# m1284prog.net
KiCad netlist of a schematic drawn in EAGLE
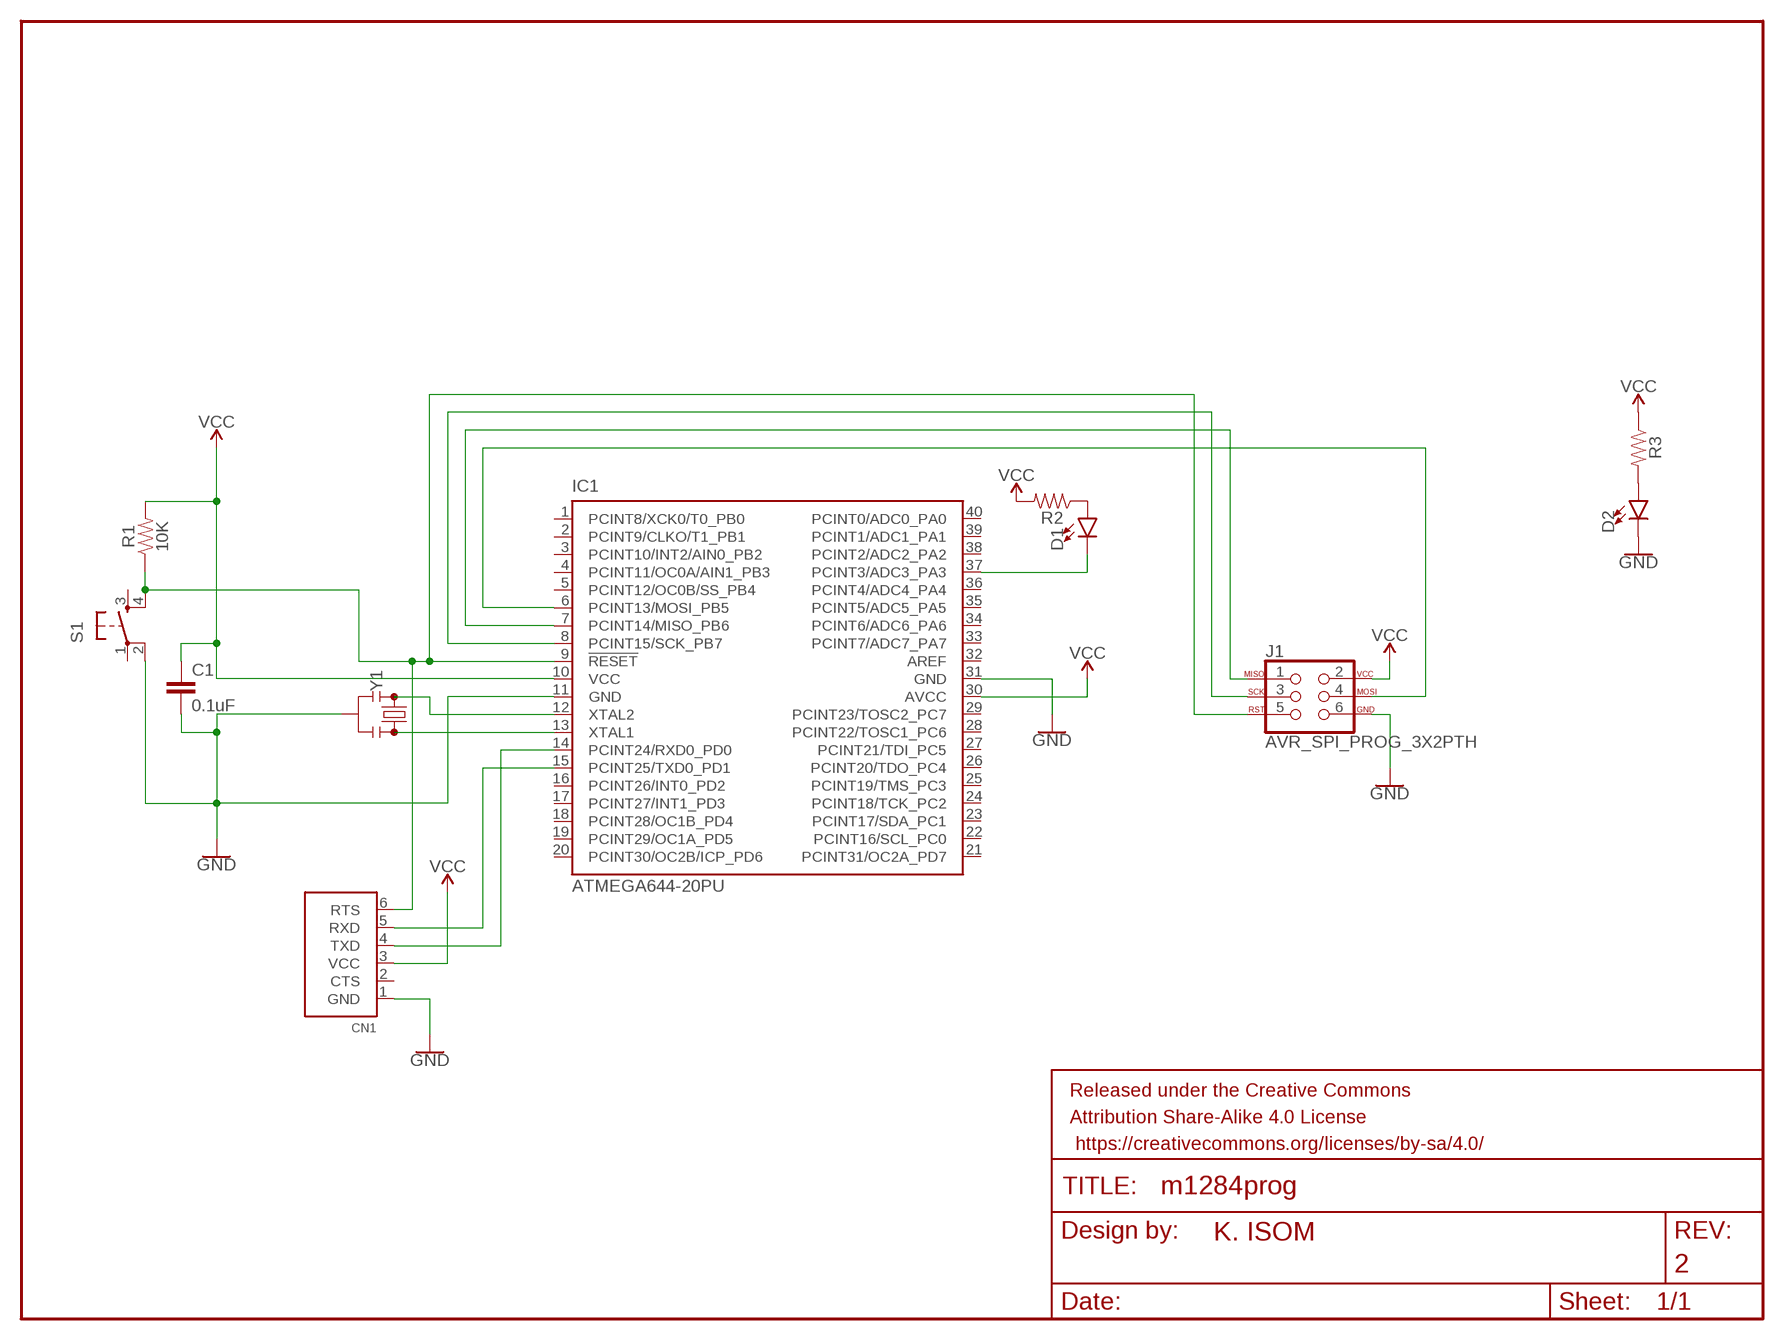
[diagram p0: schematic, sheet 1]

(export (version "E")
  (design (tool "Eeschema 10.0.6"))
  (components
    (comp (ref "C1")
      (value "0.1uF")
      (footprint "eagle-import:C2.5-3")
      (libsource (lib "eagle-import") (part "C2,5-3"))
    )
    (comp (ref "CN1")
      (value "FTDIUSBCABLE")
      (footprint "eagle-import:1X06_ROUND")
      (libsource (lib "eagle-import") (part "FTDIUSBCABLE"))
    )
    (comp (ref "D1")
      (value "LED3MM")
      (footprint "eagle-import:LED_3MM")
      (libsource (lib "eagle-import") (part "LED3MM"))
    )
    (comp (ref "D2")
      (value "LED3MM")
      (footprint "eagle-import:LED_3MM")
      (libsource (lib "eagle-import") (part "LED3MM"))
    )
    (comp (ref "FRAME1")
      (value "FRAME-LETTER")
      (footprint "eagle-import:CREATIVE_COMMONS")
      (fields (field (name "DESIGNER") "K. ISOM") (field (name "REV") "2"))
      (libsource (lib "eagle-import") (part "FRAME-LETTER"))
    )
    (comp (ref "IC1")
      (value "ATMEGA644-20PU")
      (footprint "eagle-import:DIL40")
      (libsource (lib "eagle-import") (part "ATMEGA644-PU20"))
    )
    (comp (ref "J1")
      (value "AVR_SPI_PROG_3X2PTH")
      (footprint "eagle-import:2X3")
      (libsource (lib "eagle-import") (part "AVR_SPI_PROG_3X2PTH"))
    )
    (comp (ref "R1")
      (value "10K")
      (footprint "eagle-import:AXIAL-0.3")
      (libsource (lib "eagle-import") (part "RESISTORAXIAL-0.3"))
    )
    (comp (ref "R2")
      (value "RESISTORAXIAL-0.3")
      (footprint "eagle-import:AXIAL-0.3")
      (libsource (lib "eagle-import") (part "RESISTORAXIAL-0.3"))
    )
    (comp (ref "R3")
      (value "RESISTORAXIAL-0.3")
      (footprint "eagle-import:AXIAL-0.3")
      (libsource (lib "eagle-import") (part "RESISTORAXIAL-0.3"))
    )
    (comp (ref "S1")
      (value "TAC_SWITCHPTH")
      (footprint "eagle-import:TACTILE-PTH")
      (libsource (lib "eagle-import") (part "TAC_SWITCHPTH"))
    )
    (comp (ref "Y1")
      (value "RESONATORPTH-7.6X3.8")
      (footprint "eagle-import:RESONATOR-PTH-7.6X3.8")
      (libsource (lib "eagle-import") (part "RESONATORPTH-7.6X3.8"))
    )
  )
  (nets
    (net (code "1") (name "GND") (class "Default")
      (node (ref "C1") (pin "2") (pinfunction "2_2") (pintype "passive"))
      (node (ref "CN1") (pin "1") (pinfunction "GND_1") (pintype "bidirectional"))
      (node (ref "D2") (pin "K") (pinfunction "C_K") (pintype "passive"))
      (node (ref "IC1") (pin "11") (pinfunction "GND_11") (pintype "power_in"))
      (node (ref "IC1") (pin "31") (pinfunction "GND_31") (pintype "power_in"))
      (node (ref "J1") (pin "6") (pinfunction "6_6") (pintype "passive"))
      (node (ref "S1") (pin "2") (pinfunction "2_2") (pintype "passive"))
      (node (ref "Y1") (pin "2") (pinfunction "2_2") (pintype "passive"))
    )
    (net (code "2") (name "Net-(CN1-RTS)") (class "Default")
      (node (ref "CN1") (pin "6") (pinfunction "RTS_6") (pintype "bidirectional"))
      (node (ref "IC1") (pin "9") (pinfunction "~{RESET}_9") (pintype "input"))
      (node (ref "J1") (pin "5") (pinfunction "5_5") (pintype "passive"))
      (node (ref "R1") (pin "P$1") (pinfunction "1_P$1") (pintype "passive"))
      (node (ref "S1") (pin "4") (pinfunction "4_4") (pintype "passive"))
    )
    (net (code "3") (name "Net-(CN1-RXD)") (class "Default")
      (node (ref "CN1") (pin "5") (pinfunction "RXD_5") (pintype "bidirectional"))
      (node (ref "IC1") (pin "15") (pinfunction "PCINT25/TXD0_PD1_15") (pintype "bidirectional"))
    )
    (net (code "4") (name "Net-(CN1-TXD)") (class "Default")
      (node (ref "CN1") (pin "4") (pinfunction "TXD_4") (pintype "bidirectional"))
      (node (ref "IC1") (pin "14") (pinfunction "PCINT24/RXD0_PD0_14") (pintype "bidirectional"))
    )
    (net (code "5") (name "Net-(D1-C)") (class "Default")
      (node (ref "D1") (pin "K") (pinfunction "C_K") (pintype "passive"))
      (node (ref "IC1") (pin "37") (pinfunction "PCINT3/ADC3_PA3_37") (pintype "bidirectional"))
    )
    (net (code "6") (name "Net-(IC1-PCINT13{slash}MOSI_PB5)") (class "Default")
      (node (ref "IC1") (pin "6") (pinfunction "PCINT13/MOSI_PB5_6") (pintype "bidirectional"))
      (node (ref "J1") (pin "4") (pinfunction "4_4") (pintype "passive"))
    )
    (net (code "7") (name "Net-(IC1-PCINT14{slash}MISO_PB6)") (class "Default")
      (node (ref "IC1") (pin "7") (pinfunction "PCINT14/MISO_PB6_7") (pintype "bidirectional"))
      (node (ref "J1") (pin "1") (pinfunction "1_1") (pintype "passive"))
    )
    (net (code "8") (name "Net-(IC1-PCINT15{slash}SCK_PB7)") (class "Default")
      (node (ref "IC1") (pin "8") (pinfunction "PCINT15/SCK_PB7_8") (pintype "bidirectional"))
      (node (ref "J1") (pin "3") (pinfunction "3_3") (pintype "passive"))
    )
    (net (code "9") (name "Net-(IC1-XTAL1)") (class "Default")
      (node (ref "IC1") (pin "13") (pinfunction "XTAL1_13") (pintype "input"))
      (node (ref "Y1") (pin "3") (pinfunction "3_3") (pintype "passive"))
    )
    (net (code "10") (name "Net-(IC1-XTAL2)") (class "Default")
      (node (ref "IC1") (pin "12") (pinfunction "XTAL2_12") (pintype "output"))
      (node (ref "Y1") (pin "1") (pinfunction "1_1") (pintype "passive"))
    )
    (net (code "11") (name "Net-(R2-1)") (class "Default")
      (node (ref "D1") (pin "A") (pinfunction "A_A") (pintype "passive"))
      (node (ref "R2") (pin "P$1") (pinfunction "1_P$1") (pintype "passive"))
    )
    (net (code "12") (name "Net-(R3-2)") (class "Default")
      (node (ref "D2") (pin "A") (pinfunction "A_A") (pintype "passive"))
      (node (ref "R3") (pin "P$2") (pinfunction "2_P$2") (pintype "passive"))
    )
    (net (code "13") (name "VCC") (class "Default")
      (node (ref "C1") (pin "1") (pinfunction "1_1") (pintype "passive"))
      (node (ref "CN1") (pin "3") (pinfunction "VCC_3") (pintype "bidirectional"))
      (node (ref "IC1") (pin "10") (pinfunction "VCC_10") (pintype "power_in"))
      (node (ref "IC1") (pin "30") (pinfunction "AVCC_30") (pintype "power_in"))
      (node (ref "J1") (pin "2") (pinfunction "2_2") (pintype "passive"))
      (node (ref "R1") (pin "P$2") (pinfunction "2_P$2") (pintype "passive"))
      (node (ref "R2") (pin "P$2") (pinfunction "2_P$2") (pintype "passive"))
      (node (ref "R3") (pin "P$1") (pinfunction "1_P$1") (pintype "passive"))
    )
    (net (code "14") (name "unconnected-(CN1-CTS-Pad2)") (class "Default")
      (node (ref "CN1") (pin "2") (pinfunction "CTS_2") (pintype "bidirectional"))
    )
    (net (code "15") (name "unconnected-(IC1-AREF-Pad32)") (class "Default")
      (node (ref "IC1") (pin "32") (pinfunction "AREF_32") (pintype "passive"))
    )
    (net (code "16") (name "unconnected-(IC1-PCINT0{slash}ADC0_PA0-Pad40)") (class "Default")
      (node (ref "IC1") (pin "40") (pinfunction "PCINT0/ADC0_PA0_40") (pintype "bidirectional"))
    )
    (net (code "17") (name "unconnected-(IC1-PCINT1{slash}ADC1_PA1-Pad39)") (class "Default")
      (node (ref "IC1") (pin "39") (pinfunction "PCINT1/ADC1_PA1_39") (pintype "bidirectional"))
    )
    (net (code "18") (name "unconnected-(IC1-PCINT2{slash}ADC2_PA2-Pad38)") (class "Default")
      (node (ref "IC1") (pin "38") (pinfunction "PCINT2/ADC2_PA2_38") (pintype "bidirectional"))
    )
    (net (code "19") (name "unconnected-(IC1-PCINT4{slash}ADC4_PA4-Pad36)") (class "Default")
      (node (ref "IC1") (pin "36") (pinfunction "PCINT4/ADC4_PA4_36") (pintype "bidirectional"))
    )
    (net (code "20") (name "unconnected-(IC1-PCINT5{slash}ADC5_PA5-Pad35)") (class "Default")
      (node (ref "IC1") (pin "35") (pinfunction "PCINT5/ADC5_PA5_35") (pintype "bidirectional"))
    )
    (net (code "21") (name "unconnected-(IC1-PCINT6{slash}ADC6_PA6-Pad34)") (class "Default")
      (node (ref "IC1") (pin "34") (pinfunction "PCINT6/ADC6_PA6_34") (pintype "bidirectional"))
    )
    (net (code "22") (name "unconnected-(IC1-PCINT7{slash}ADC7_PA7-Pad33)") (class "Default")
      (node (ref "IC1") (pin "33") (pinfunction "PCINT7/ADC7_PA7_33") (pintype "bidirectional"))
    )
    (net (code "23") (name "unconnected-(IC1-PCINT8{slash}XCK0{slash}T0_PB0-Pad1)") (class "Default")
      (node (ref "IC1") (pin "1") (pinfunction "PCINT8/XCK0/T0_PB0_1") (pintype "bidirectional"))
    )
    (net (code "24") (name "unconnected-(IC1-PCINT9{slash}CLKO{slash}T1_PB1-Pad2)") (class "Default")
      (node (ref "IC1") (pin "2") (pinfunction "PCINT9/CLKO/T1_PB1_2") (pintype "bidirectional"))
    )
    (net (code "25") (name "unconnected-(IC1-PCINT10{slash}INT2{slash}AIN0_PB2-Pad3)") (class "Default")
      (node (ref "IC1") (pin "3") (pinfunction "PCINT10/INT2/AIN0_PB2_3") (pintype "bidirectional"))
    )
    (net (code "26") (name "unconnected-(IC1-PCINT11{slash}OC0A{slash}AIN1_PB3-Pad4)") (class "Default")
      (node (ref "IC1") (pin "4") (pinfunction "PCINT11/OC0A/AIN1_PB3_4") (pintype "bidirectional"))
    )
    (net (code "27") (name "unconnected-(IC1-PCINT12{slash}OC0B{slash}SS_PB4-Pad5)") (class "Default")
      (node (ref "IC1") (pin "5") (pinfunction "PCINT12/OC0B/SS_PB4_5") (pintype "bidirectional"))
    )
    (net (code "28") (name "unconnected-(IC1-PCINT16{slash}SCL_PC0-Pad22)") (class "Default")
      (node (ref "IC1") (pin "22") (pinfunction "PCINT16/SCL_PC0_22") (pintype "bidirectional"))
    )
    (net (code "29") (name "unconnected-(IC1-PCINT17{slash}SDA_PC1-Pad23)") (class "Default")
      (node (ref "IC1") (pin "23") (pinfunction "PCINT17/SDA_PC1_23") (pintype "bidirectional"))
    )
    (net (code "30") (name "unconnected-(IC1-PCINT18{slash}TCK_PC2-Pad24)") (class "Default")
      (node (ref "IC1") (pin "24") (pinfunction "PCINT18/TCK_PC2_24") (pintype "bidirectional"))
    )
    (net (code "31") (name "unconnected-(IC1-PCINT19{slash}TMS_PC3-Pad25)") (class "Default")
      (node (ref "IC1") (pin "25") (pinfunction "PCINT19/TMS_PC3_25") (pintype "bidirectional"))
    )
    (net (code "32") (name "unconnected-(IC1-PCINT20{slash}TDO_PC4-Pad26)") (class "Default")
      (node (ref "IC1") (pin "26") (pinfunction "PCINT20/TDO_PC4_26") (pintype "bidirectional"))
    )
    (net (code "33") (name "unconnected-(IC1-PCINT21{slash}TDI_PC5-Pad27)") (class "Default")
      (node (ref "IC1") (pin "27") (pinfunction "PCINT21/TDI_PC5_27") (pintype "bidirectional"))
    )
    (net (code "34") (name "unconnected-(IC1-PCINT22{slash}TOSC1_PC6-Pad28)") (class "Default")
      (node (ref "IC1") (pin "28") (pinfunction "PCINT22/TOSC1_PC6_28") (pintype "bidirectional"))
    )
    (net (code "35") (name "unconnected-(IC1-PCINT23{slash}TOSC2_PC7-Pad29)") (class "Default")
      (node (ref "IC1") (pin "29") (pinfunction "PCINT23/TOSC2_PC7_29") (pintype "bidirectional"))
    )
    (net (code "36") (name "unconnected-(IC1-PCINT26{slash}INT0_PD2-Pad16)") (class "Default")
      (node (ref "IC1") (pin "16") (pinfunction "PCINT26/INT0_PD2_16") (pintype "bidirectional"))
    )
    (net (code "37") (name "unconnected-(IC1-PCINT27{slash}INT1_PD3-Pad17)") (class "Default")
      (node (ref "IC1") (pin "17") (pinfunction "PCINT27/INT1_PD3_17") (pintype "bidirectional"))
    )
    (net (code "38") (name "unconnected-(IC1-PCINT28{slash}OC1B_PD4-Pad18)") (class "Default")
      (node (ref "IC1") (pin "18") (pinfunction "PCINT28/OC1B_PD4_18") (pintype "bidirectional"))
    )
    (net (code "39") (name "unconnected-(IC1-PCINT29{slash}OC1A_PD5-Pad19)") (class "Default")
      (node (ref "IC1") (pin "19") (pinfunction "PCINT29/OC1A_PD5_19") (pintype "bidirectional"))
    )
    (net (code "40") (name "unconnected-(IC1-PCINT30{slash}OC2B{slash}ICP_PD6-Pad20)") (class "Default")
      (node (ref "IC1") (pin "20") (pinfunction "PCINT30/OC2B/ICP_PD6_20") (pintype "bidirectional"))
    )
    (net (code "41") (name "unconnected-(IC1-PCINT31{slash}OC2A_PD7-Pad21)") (class "Default")
      (node (ref "IC1") (pin "21") (pinfunction "PCINT31/OC2A_PD7_21") (pintype "bidirectional"))
    )
    (net (code "42") (name "unconnected-(S1-Pad1)") (class "Default")
      (node (ref "S1") (pin "1") (pinfunction "1_1") (pintype "passive"))
    )
    (net (code "43") (name "unconnected-(S1-Pad3)") (class "Default")
      (node (ref "S1") (pin "3") (pinfunction "3_3") (pintype "passive"))
    )
  )
)
